# DarkDetector.net
KiCad netlist of a schematic drawn in EasyEDA
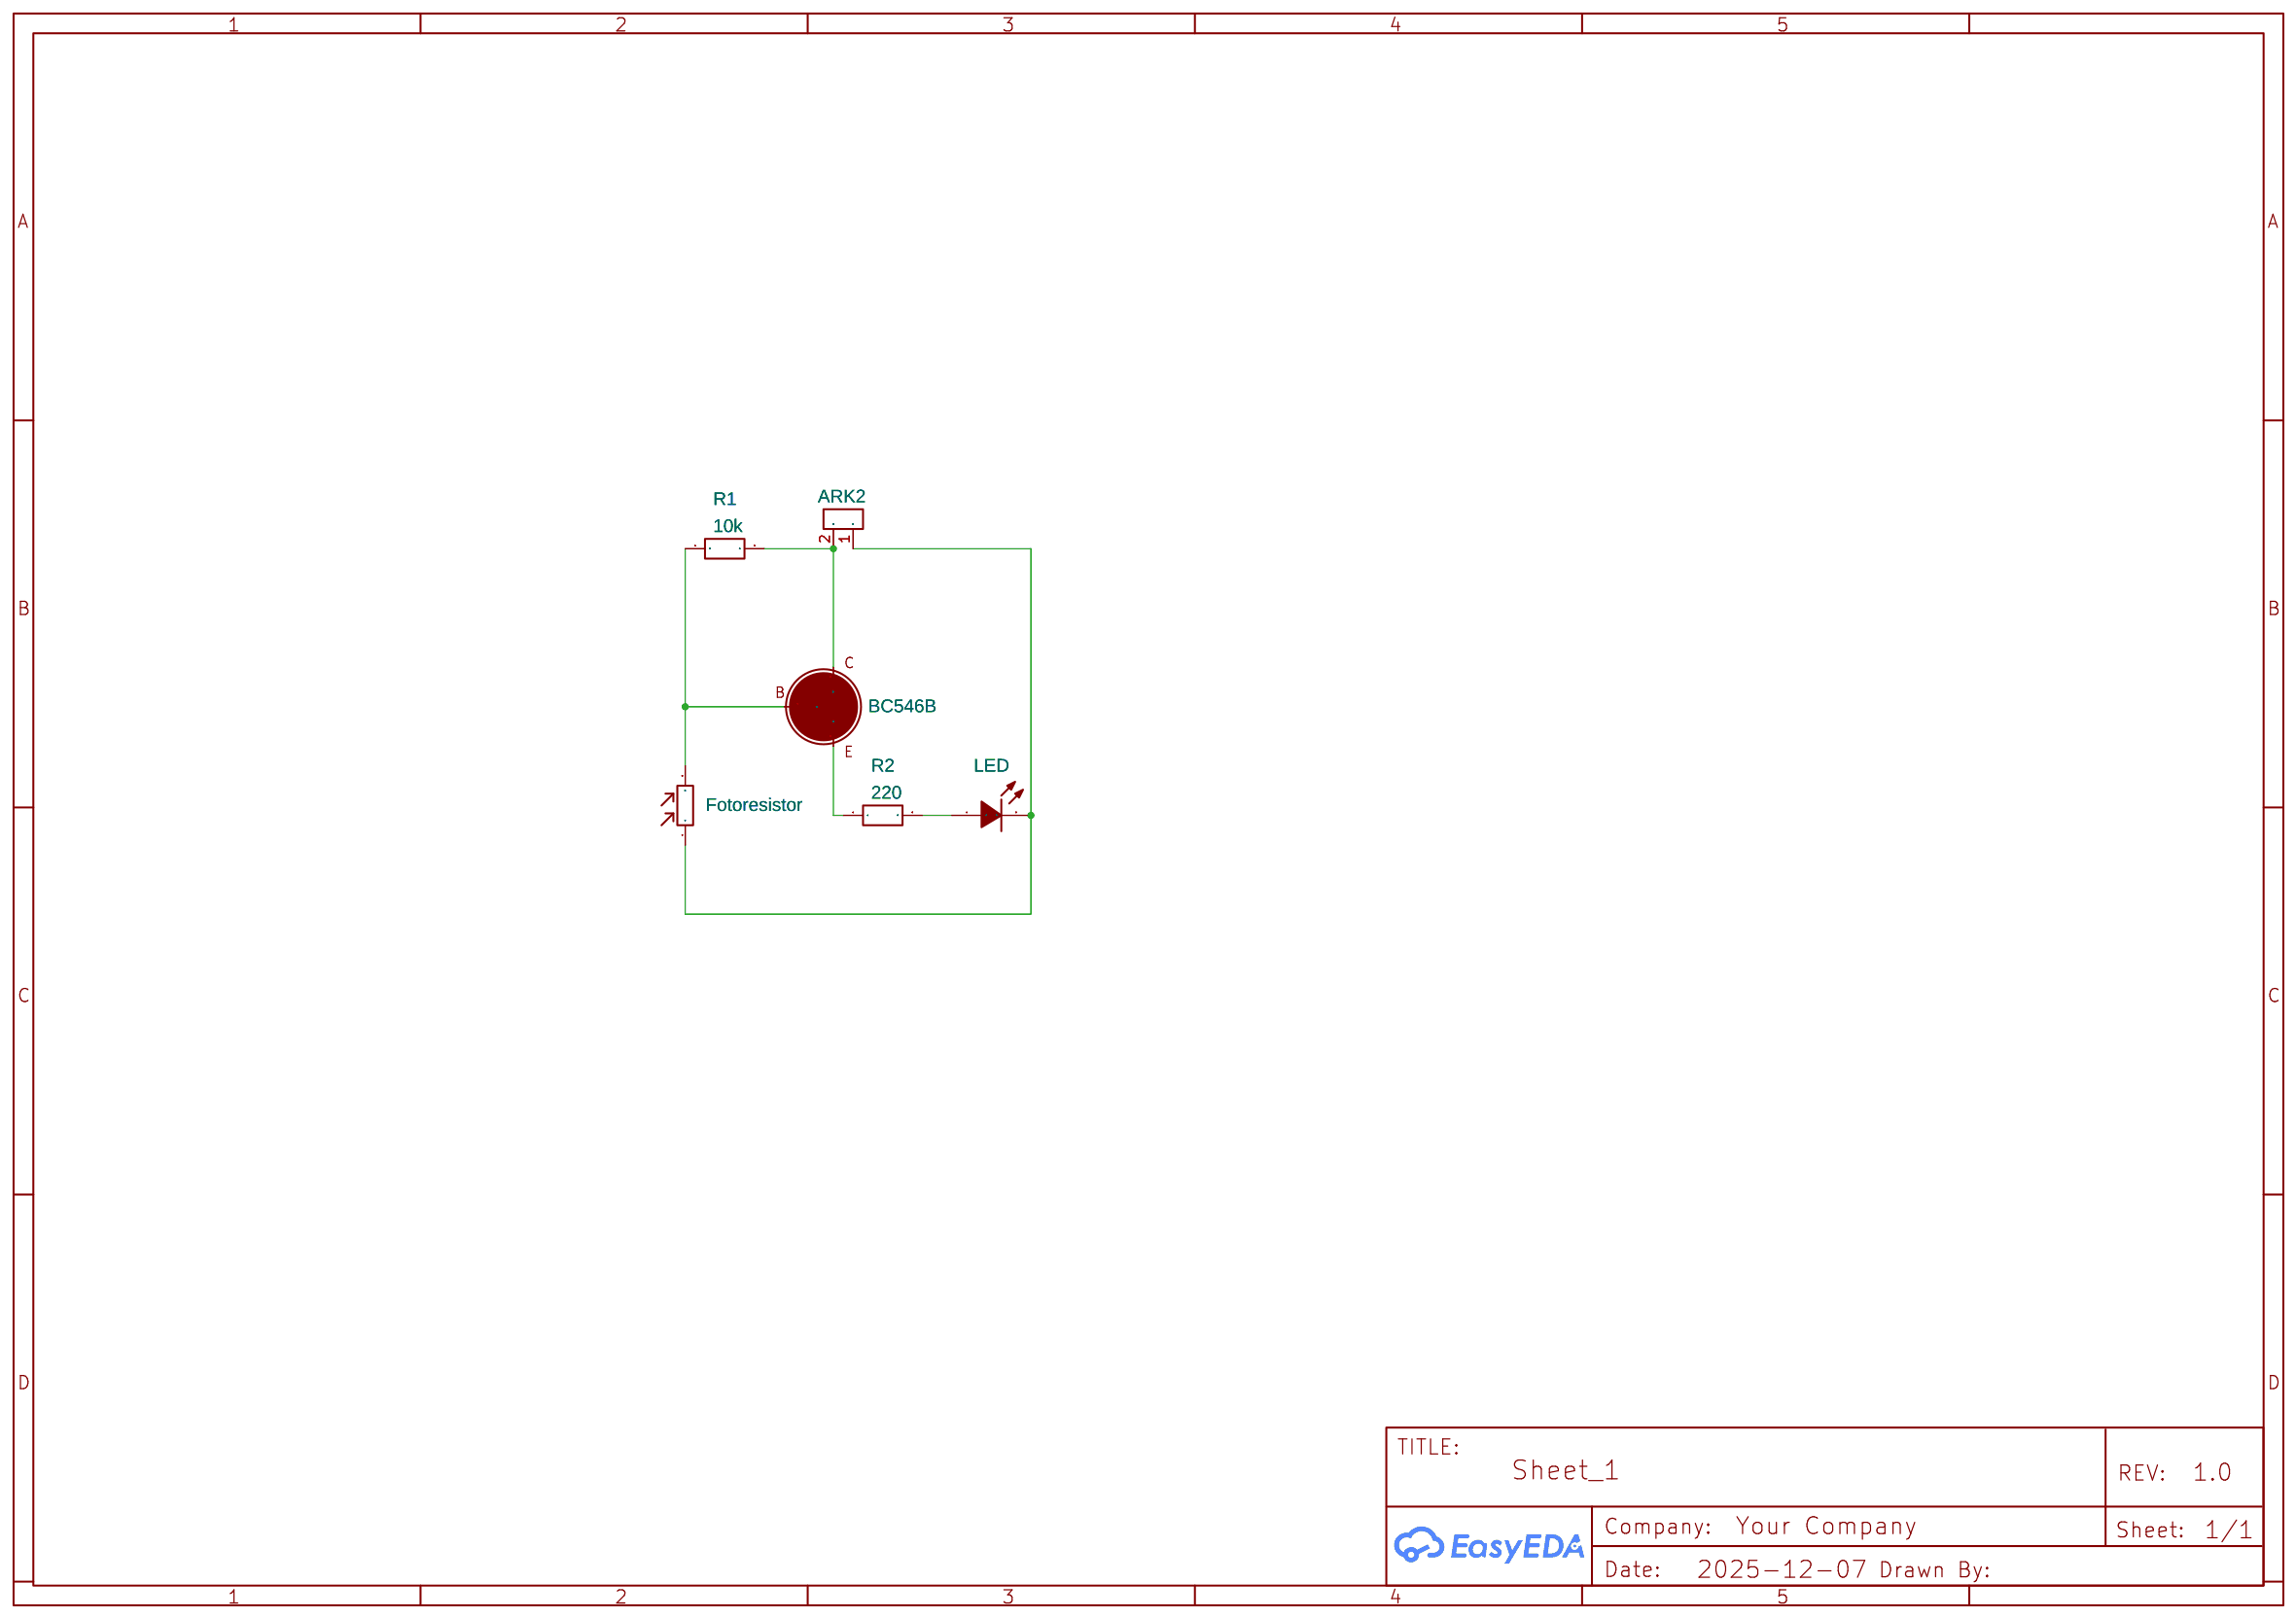
[diagram p0: schematic sheet]

(export (version "E")
  (design (tool "Eeschema 10.0.6"))
  (components
    (comp (ref "CON1") (value "ARK2") (libsource (lib "") (part "ARK2")))
    (comp (ref "LED")
      (value "RED")
      (fields
        (field (name "Manufacturer Part") "19-217/R6C-AL1M2VY/3T")
        (field (name "Manufacturer") "EVERLIGHT(台湾亿光)")
      )
      (libsource (lib "") (part "LED-0603_R"))
    )
    (comp (ref "Q1")
      (value "BC546B")
      (fields (field (name "Manufacturer Part") "BC337") (field (name "Manufacturer") "CJ"))
      (libsource (lib "") (part "BC546B"))
    )
    (comp (ref "R1") (value "10k") (libsource (lib "") (part "R_0603_EU")))
    (comp (ref "R2") (value "220") (libsource (lib "") (part "R_0603_EU")))
    (comp (ref "U1") (value "Fotoresistor") (libsource (lib "") (part "Fotoresistor G")))
  )
  (nets
    (net (code "1") (name "Net-(CON1-Pad1)") (class "Default")
      (node (ref "CON1") (pin "1") (pinfunction "1_1") (pintype "unspecified"))
      (node (ref "LED") (pin "2") (pinfunction "2_2") (pintype "unspecified"))
      (node (ref "U1") (pin "1") (pinfunction "1_1") (pintype "input"))
    )
    (net (code "2") (name "Net-(LED-Pad1)") (class "Default")
      (node (ref "LED") (pin "1") (pinfunction "1_1") (pintype "unspecified"))
      (node (ref "R2") (pin "2") (pinfunction "2_2") (pintype "unspecified"))
    )
    (net (code "3") (name "Net-(Q1-B)") (class "Default")
      (node (ref "Q1") (pin "2") (pinfunction "B_2") (pintype "unspecified"))
      (node (ref "R1") (pin "1") (pinfunction "1_1") (pintype "unspecified"))
      (node (ref "U1") (pin "2") (pinfunction "2_2") (pintype "input"))
    )
    (net (code "4") (name "Net-(Q1-C)") (class "Default")
      (node (ref "CON1") (pin "2") (pinfunction "2_2") (pintype "unspecified"))
      (node (ref "Q1") (pin "1") (pinfunction "C_1") (pintype "unspecified"))
      (node (ref "R1") (pin "2") (pinfunction "2_2") (pintype "unspecified"))
    )
    (net (code "5") (name "Net-(Q1-E)") (class "Default")
      (node (ref "Q1") (pin "3") (pinfunction "E_3") (pintype "unspecified"))
      (node (ref "R2") (pin "1") (pinfunction "1_1") (pintype "unspecified"))
    )
  )
)
